# 1B_dual_supply.net
KiCad netlist of a schematic drawn in EAGLE
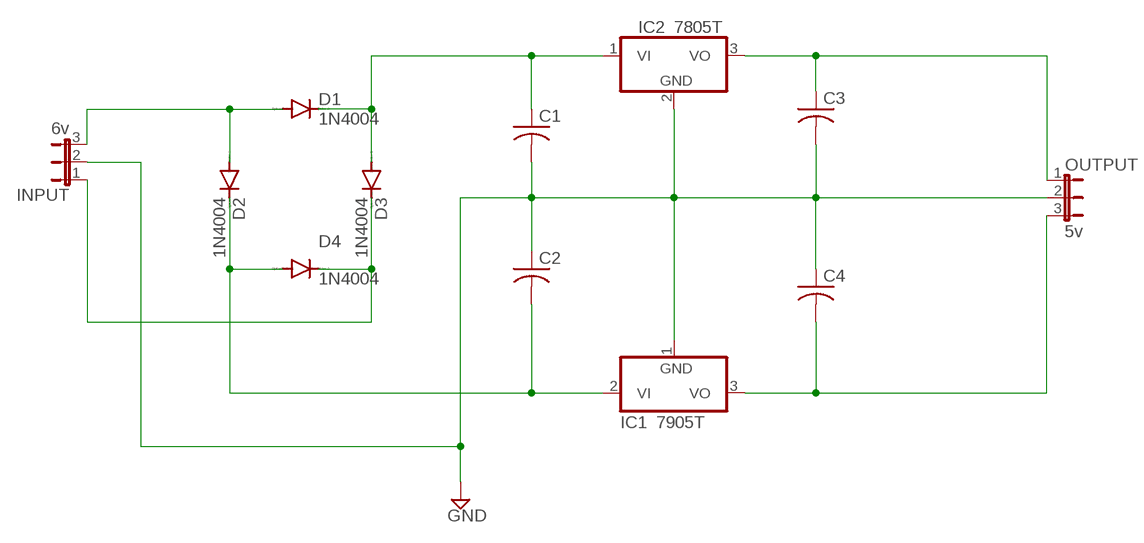
[diagram p0: schematic, sheet 1]

(export (version "E")
  (design (tool "Eeschema 10.0.6"))
  (components
    (comp (ref "C1")
      (value "C-US150-054X183")
      (footprint "eagle-import:C150-054X183")
      (libsource (lib "eagle-import") (part "C-US150-054X183"))
    )
    (comp (ref "C2")
      (value "C-US150-054X183")
      (footprint "eagle-import:C150-054X183")
      (libsource (lib "eagle-import") (part "C-US150-054X183"))
    )
    (comp (ref "C3")
      (value "C-US150-054X183")
      (footprint "eagle-import:C150-054X183")
      (libsource (lib "eagle-import") (part "C-US150-054X183"))
    )
    (comp (ref "C4")
      (value "C-US150-054X183")
      (footprint "eagle-import:C150-054X183")
      (libsource (lib "eagle-import") (part "C-US150-054X183"))
    )
    (comp (ref "D1")
      (value "1N4004")
      (footprint "eagle-import:DO41-10")
      (libsource (lib "eagle-import") (part "1N4004"))
    )
    (comp (ref "D2")
      (value "1N4004")
      (footprint "eagle-import:DO41-10")
      (libsource (lib "eagle-import") (part "1N4004"))
    )
    (comp (ref "D3")
      (value "1N4004")
      (footprint "eagle-import:DO41-10")
      (libsource (lib "eagle-import") (part "1N4004"))
    )
    (comp (ref "D4")
      (value "1N4004")
      (footprint "eagle-import:DO41-10")
      (libsource (lib "eagle-import") (part "1N4004"))
    )
    (comp (ref "IC1")
      (value "7905T")
      (footprint "eagle-import:TO220H")
      (libsource (lib "eagle-import") (part "79T08"))
    )
    (comp (ref "IC2")
      (value "7805T")
      (footprint "eagle-import:TO220H")
      (libsource (lib "eagle-import") (part "78T05"))
    )
    (comp (ref "INPUT")
      (value "6v")
      (footprint "eagle-import:JP2")
      (libsource (lib "eagle-import") (part "JP2E"))
    )
    (comp (ref "OUTPUT")
      (value "5v")
      (footprint "eagle-import:JP2")
      (libsource (lib "eagle-import") (part "JP2E"))
    )
  )
  (nets
    (net (code "1") (name "GND") (class "Default")
      (node (ref "C1") (pin "2") (pinfunction "2_2") (pintype "passive"))
      (node (ref "C2") (pin "1") (pinfunction "1_1") (pintype "passive"))
      (node (ref "C3") (pin "2") (pinfunction "2_2") (pintype "passive"))
      (node (ref "C4") (pin "1") (pinfunction "1_1") (pintype "passive"))
      (node (ref "IC1") (pin "1") (pinfunction "GND_1") (pintype "passive"))
      (node (ref "IC2") (pin "2") (pinfunction "GND_2") (pintype "passive"))
      (node (ref "INPUT") (pin "2") (pinfunction "2_2") (pintype "passive"))
      (node (ref "OUTPUT") (pin "2") (pinfunction "2_2") (pintype "passive"))
    )
    (net (code "2") (name "Net-(D1-PadA)") (class "Default")
      (node (ref "D1") (pin "A") (pinfunction "A_A") (pintype "passive"))
      (node (ref "D2") (pin "A") (pinfunction "A_A") (pintype "passive"))
      (node (ref "INPUT") (pin "3") (pinfunction "3_3") (pintype "passive"))
    )
    (net (code "3") (name "Net-(D3-PadC)") (class "Default")
      (node (ref "D3") (pin "C") (pinfunction "C_C") (pintype "passive"))
      (node (ref "D4") (pin "C") (pinfunction "C_C") (pintype "passive"))
      (node (ref "INPUT") (pin "1") (pinfunction "1_1") (pintype "passive"))
    )
    (net (code "4") (name "Net-(IC1-VI)") (class "Default")
      (node (ref "C2") (pin "2") (pinfunction "2_2") (pintype "passive"))
      (node (ref "D2") (pin "C") (pinfunction "C_C") (pintype "passive"))
      (node (ref "D4") (pin "A") (pinfunction "A_A") (pintype "passive"))
      (node (ref "IC1") (pin "2") (pinfunction "VI_2") (pintype "input"))
    )
    (net (code "5") (name "Net-(IC1-VO)") (class "Default")
      (node (ref "C4") (pin "2") (pinfunction "2_2") (pintype "passive"))
      (node (ref "IC1") (pin "3") (pinfunction "VO_3") (pintype "passive"))
      (node (ref "OUTPUT") (pin "3") (pinfunction "3_3") (pintype "passive"))
    )
    (net (code "6") (name "Net-(IC2-VI)") (class "Default")
      (node (ref "C1") (pin "1") (pinfunction "1_1") (pintype "passive"))
      (node (ref "D1") (pin "C") (pinfunction "C_C") (pintype "passive"))
      (node (ref "D3") (pin "A") (pinfunction "A_A") (pintype "passive"))
      (node (ref "IC2") (pin "1") (pinfunction "VI_1") (pintype "input"))
    )
    (net (code "7") (name "Net-(IC2-VO)") (class "Default")
      (node (ref "C3") (pin "1") (pinfunction "1_1") (pintype "passive"))
      (node (ref "IC2") (pin "3") (pinfunction "VO_3") (pintype "passive"))
      (node (ref "OUTPUT") (pin "1") (pinfunction "1_1") (pintype "passive"))
    )
  )
)
